# GSM_SIM_Socket.net
KiCad netlist of a schematic drawn in Altium Designer
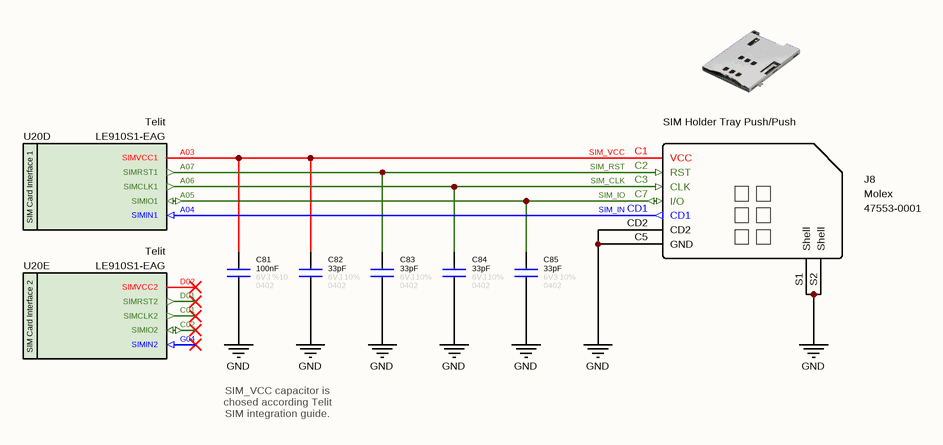
[diagram p0: GSM SIM Socket.SchDoc]

(export (version "E")
  (design (tool "Eeschema 10.0.6"))
  (components
    (comp (ref "C81")
      (value "100nF")
      (footprint "CAPACITOR_0402")
      (description "Capacitor - 100nF [0402-6V3] (Ceramic)")
      (fields
        (field (name "MANUFACTURER PART NUMBER") "04026D104KAT4A")
        (field (name "TOLERANCE") "%10")
        (field (name "VOLTAGE") "6V3")
        (field (name "CASE") "0402")
        (field (name "Comment") "Capacitor - 100nF [0402] (Ceramic)")
      )
      (libsource (lib "Akkoyun") (part "Capacitor - 100nF [0402-6V3]"))
    )
    (comp (ref "C82")
      (value "33pF")
      (footprint "CAPACITOR_0402")
      (description "Capacitor - 33pF [0402] (Ceramic)")
      (fields
        (field (name "MANUFACTURER PART NUMBER") "C0402C330J9RACAUTO")
        (field (name "TOLERANCE") "10%")
        (field (name "CASE") "0402")
        (field (name "VOLTAGE") "6V3")
      )
      (libsource (lib "Akkoyun") (part "Capacitor - 33pF [0402-6V3]"))
    )
    (comp (ref "C83")
      (value "33pF")
      (footprint "CAPACITOR_0402")
      (description "Capacitor - 33pF [0402] (Ceramic)")
      (fields
        (field (name "MANUFACTURER PART NUMBER") "C0402C330J9RACAUTO")
        (field (name "TOLERANCE") "10%")
        (field (name "CASE") "0402")
        (field (name "VOLTAGE") "6V3")
      )
      (libsource (lib "Akkoyun") (part "Capacitor - 33pF [0402-6V3]"))
    )
    (comp (ref "C84")
      (value "33pF")
      (footprint "CAPACITOR_0402")
      (description "Capacitor - 33pF [0402] (Ceramic)")
      (fields
        (field (name "MANUFACTURER PART NUMBER") "C0402C330J9RACAUTO")
        (field (name "TOLERANCE") "10%")
        (field (name "CASE") "0402")
        (field (name "VOLTAGE") "6V3")
      )
      (libsource (lib "Akkoyun") (part "Capacitor - 33pF [0402-6V3]"))
    )
    (comp (ref "C85")
      (value "33pF")
      (footprint "CAPACITOR_0402")
      (description "Capacitor - 33pF [0402] (Ceramic)")
      (fields
        (field (name "MANUFACTURER PART NUMBER") "C0402C330J9RACAUTO")
        (field (name "TOLERANCE") "10%")
        (field (name "CASE") "0402")
        (field (name "VOLTAGE") "6V3")
      )
      (libsource (lib "Akkoyun") (part "Capacitor - 33pF [0402-6V3]"))
    )
    (comp (ref "J8")
      (value "SIM Holder Tray")
      (footprint "CONNECTOR - SIM Card")
      (description "Memory Card Connectors ASSY 1.90 SIM CARD R IM CARD READER CONN.")
      (fields
        (field (name "CARD TYPE") "SIM Holder Tray Push/Push")
        (field (name "MANUFACTURER NAME") "Molex")
        (field (name "MANUFACTURER PART NUMBER") "47553-0001")
      )
      (libsource (lib "Akkoyun") (part "Connector - Sim Holder"))
    )
    (comp (ref "U20")
      (value "LE910S1-EAG LTE GSM Module")
      (footprint "LE910 GSM Modem")
      (description "Telit LE910S1-EAG GPRS/GNSS Module")
      (fields
        (field (name "MANUFACTURER PART NUMBER") "LE910S1-EAG")
        (field (name "MANUFACTURER NAME") "Telit")
      )
      (libsource (lib "Akkoyun") (part "IC - LE910S1-EAG"))
    )
  )
  (nets
    (net (code "1") (name "/SIM_CLK") (class "Default")
      (node (ref "C84") (pin "2") (pinfunction "2_2") (pintype "passive"))
      (node (ref "J8") (pin "C3") (pinfunction "CLK_C3") (pintype "input"))
      (node (ref "U20") (pin "A06") (pinfunction "SIMCLK1_A06") (pintype "output"))
    )
    (net (code "2") (name "/SIM_IN") (class "Default")
      (node (ref "J8") (pin "CD1") (pinfunction "CD1_CD1") (pintype "output"))
      (node (ref "U20") (pin "A04") (pinfunction "SIMIN1_A04") (pintype "input"))
    )
    (net (code "3") (name "/SIM_IO") (class "Default")
      (node (ref "C85") (pin "2") (pinfunction "2_2") (pintype "passive"))
      (node (ref "J8") (pin "C7") (pinfunction "I/O_C7") (pintype "bidirectional"))
      (node (ref "U20") (pin "A05") (pinfunction "SIMIO1_A05") (pintype "bidirectional"))
    )
    (net (code "4") (name "/SIM_RST") (class "Default")
      (node (ref "C83") (pin "2") (pinfunction "2_2") (pintype "passive"))
      (node (ref "J8") (pin "C2") (pinfunction "RST_C2") (pintype "input"))
      (node (ref "U20") (pin "A07") (pinfunction "SIMRST1_A07") (pintype "output"))
    )
    (net (code "5") (name "/SIM_VCC") (class "Default")
      (node (ref "C81") (pin "2") (pinfunction "2_2") (pintype "passive"))
      (node (ref "C82") (pin "2") (pinfunction "2_2") (pintype "passive"))
      (node (ref "J8") (pin "C1") (pinfunction "VCC_C1") (pintype "power_in"))
      (node (ref "U20") (pin "A03") (pinfunction "SIMVCC1_A03") (pintype "power_in"))
    )
    (net (code "6") (name "GND") (class "Default")
      (node (ref "C81") (pin "1") (pinfunction "1_1") (pintype "passive"))
      (node (ref "C82") (pin "1") (pinfunction "1_1") (pintype "passive"))
      (node (ref "C83") (pin "1") (pinfunction "1_1") (pintype "passive"))
      (node (ref "C84") (pin "1") (pinfunction "1_1") (pintype "passive"))
      (node (ref "C85") (pin "1") (pinfunction "1_1") (pintype "passive"))
      (node (ref "J8") (pin "C5") (pinfunction "GND_C5") (pintype "power_in"))
      (node (ref "J8") (pin "CD2") (pinfunction "CD2_CD2") (pintype "passive"))
      (node (ref "J8") (pin "S1") (pinfunction "Shell_S1") (pintype "power_in"))
      (node (ref "J8") (pin "S2") (pinfunction "Shell_S2") (pintype "power_in"))
    )
    (net (code "7") (name "unconnected-(U20E-SIMCLK2-PadC01)") (class "Default")
      (node (ref "U20") (pin "C01") (pinfunction "SIMCLK2_C01") (pintype "output+no_connect"))
    )
    (net (code "8") (name "unconnected-(U20E-SIMIN2-PadG04)") (class "Default")
      (node (ref "U20") (pin "G04") (pinfunction "SIMIN2_G04") (pintype "input+no_connect"))
    )
    (net (code "9") (name "unconnected-(U20E-SIMIO2-PadC02)") (class "Default")
      (node (ref "U20") (pin "C02") (pinfunction "SIMIO2_C02") (pintype "bidirectional+no_connect"))
    )
    (net (code "10") (name "unconnected-(U20E-SIMRST2-PadD01)") (class "Default")
      (node (ref "U20") (pin "D01") (pinfunction "SIMRST2_D01") (pintype "output+no_connect"))
    )
    (net (code "11") (name "unconnected-(U20E-SIMVCC2-PadD02)") (class "Default")
      (node (ref "U20") (pin "D02") (pinfunction "SIMVCC2_D02") (pintype "passive+no_connect"))
    )
  )
)
